# MainSchematic.net
KiCad netlist of a schematic drawn in Altium Designer
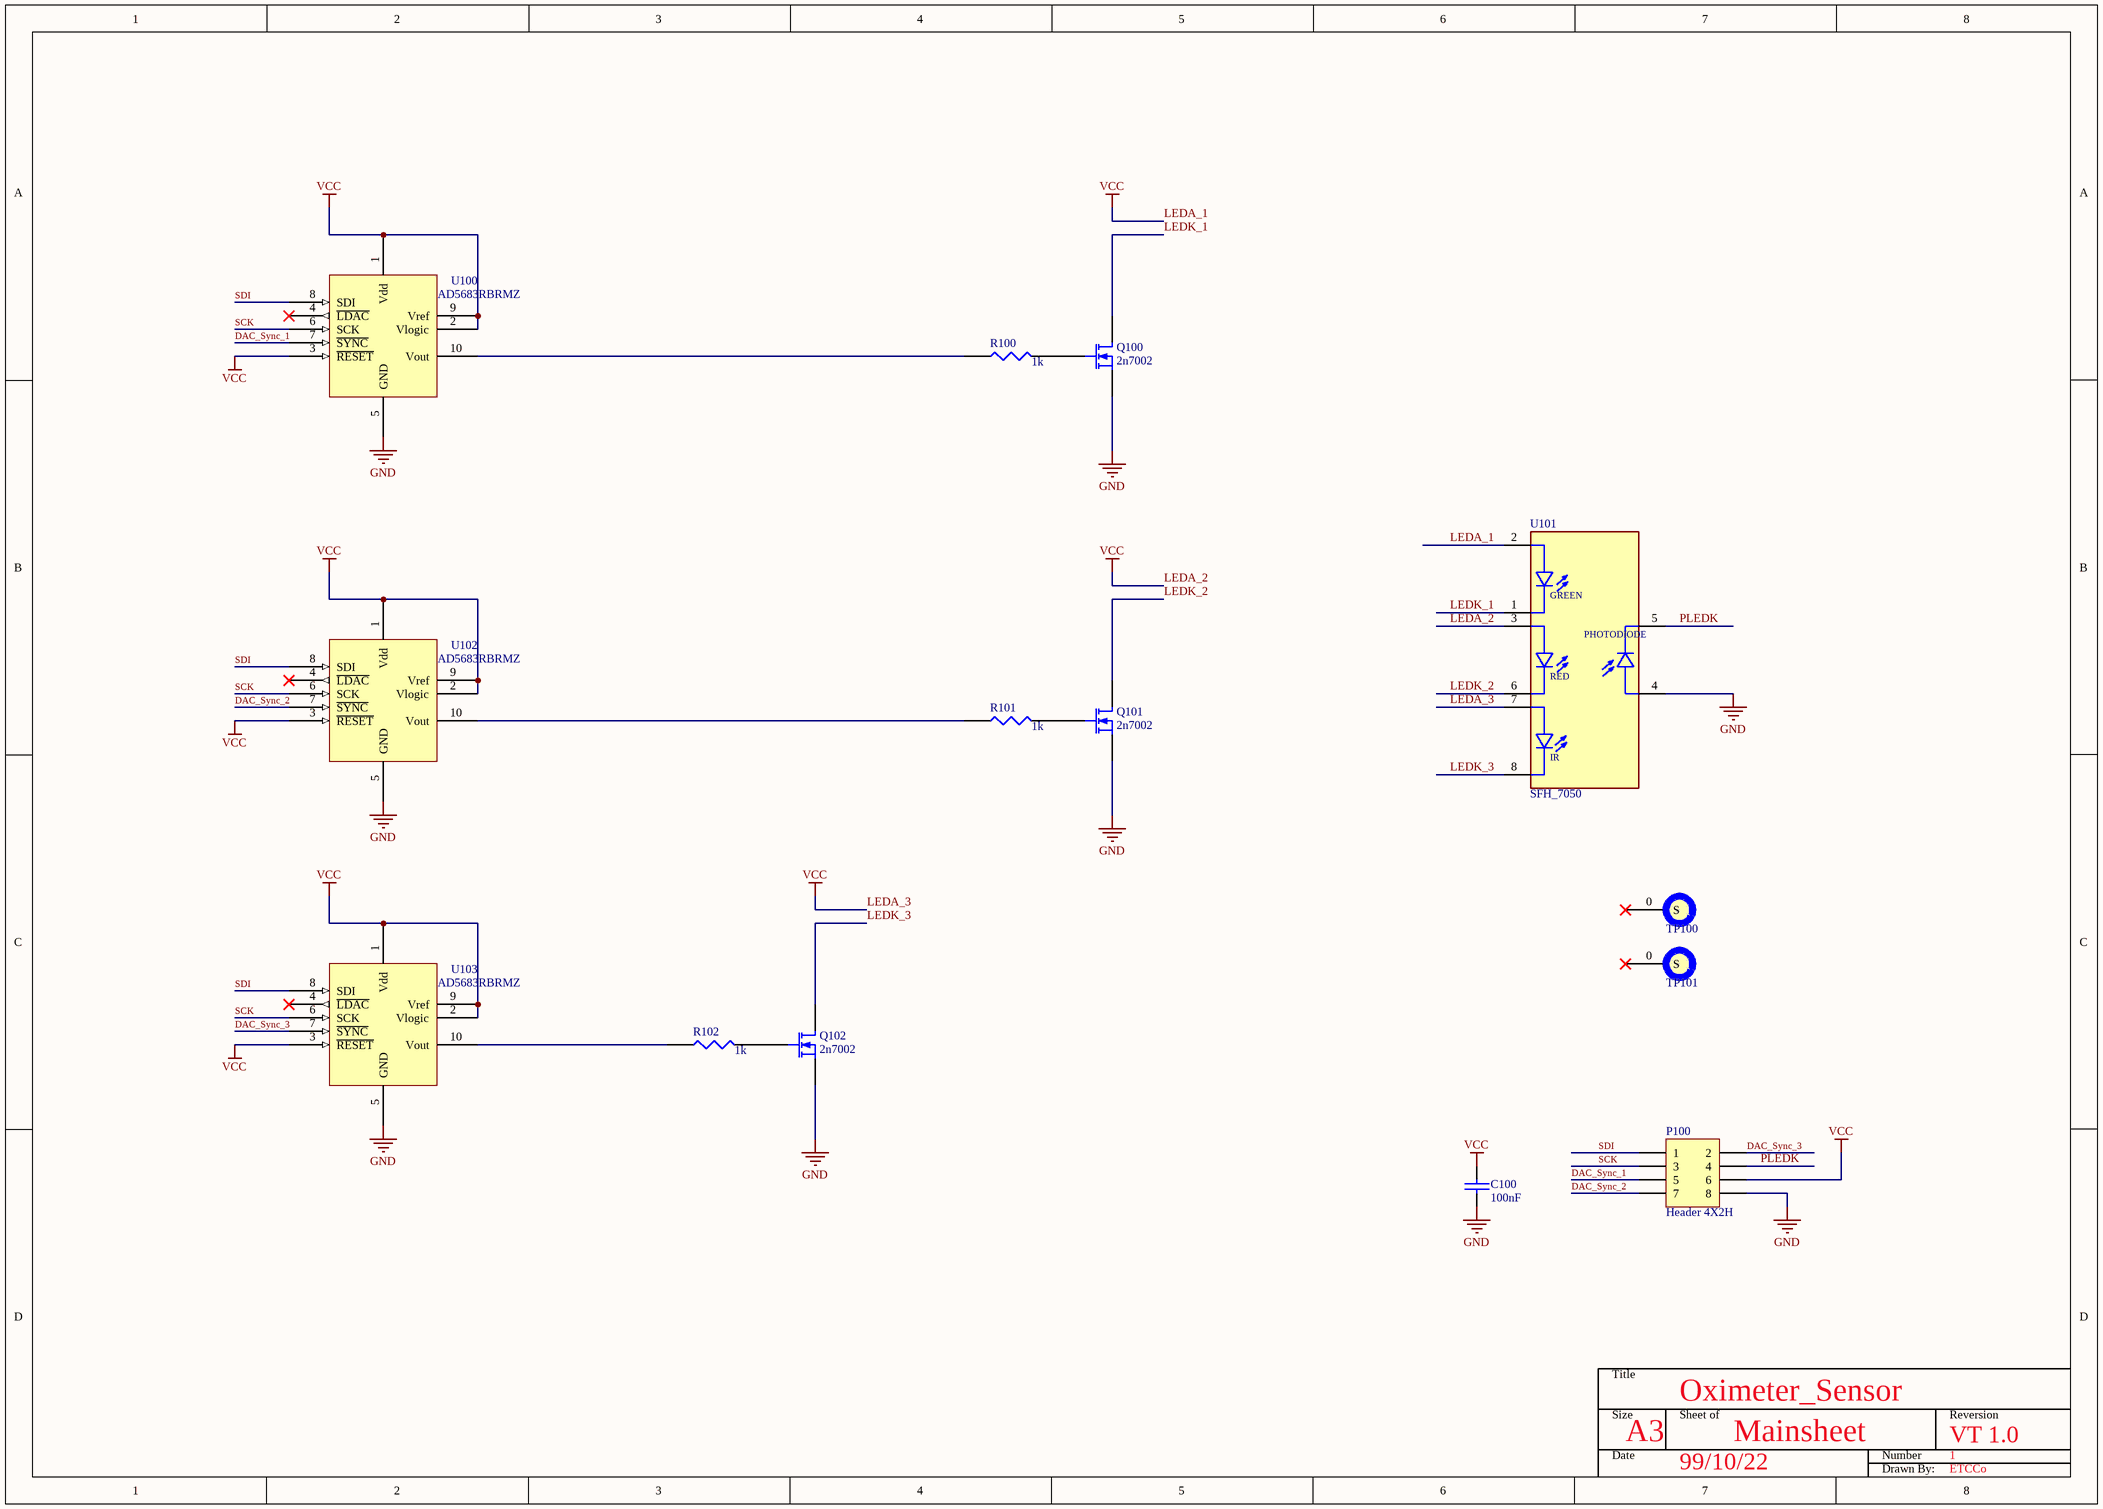
[diagram p0: MainSchematic.SchDoc]

(export (version "E")
  (design (tool "Eeschema 10.0.6"))
  (components
    (comp (ref "C100")
      (value "100nF")
      (footprint "0603-2")
      (description "Capacitor")
      (libsource (lib "*") (part "CAP"))
    )
    (comp (ref "P100")
      (value "Header 4X2H")
      (footprint "HDR2X4_edited")
      (description "Header, 4-Pin, Dual row, Right Angle")
      (fields (field (name "PUBLISHER") "Altium Limited"))
      (libsource (lib "Miscellaneous Connectors") (part "Header 4X2H"))
    )
    (comp (ref "Q100")
      (value "2n7002")
      (footprint "a_SOT23")
      (description "N-Channel MOSFET")
      (fields (field (name "PUBLISHER") "Altium Limited"))
      (libsource (lib "Miscellaneous Devices") (part "MOSFET-N"))
    )
    (comp (ref "Q101")
      (value "2n7002")
      (footprint "a_SOT23")
      (description "N-Channel MOSFET")
      (fields (field (name "PUBLISHER") "Altium Limited"))
      (libsource (lib "Miscellaneous Devices") (part "MOSFET-N"))
    )
    (comp (ref "Q102")
      (value "2n7002")
      (footprint "a_SOT23")
      (description "N-Channel MOSFET")
      (fields (field (name "PUBLISHER") "Altium Limited"))
      (libsource (lib "Miscellaneous Devices") (part "MOSFET-N"))
    )
    (comp (ref "R100") (value "1k") (footprint "0603-2") (libsource (lib "*") (part "RES1")))
    (comp (ref "R101") (value "1k") (footprint "0603-2") (libsource (lib "*") (part "RES1")))
    (comp (ref "R102") (value "1k") (footprint "0603-2") (libsource (lib "*") (part "RES1")))
    (comp (ref "TP100") (value "HOLE") (footprint "A_Ert") (libsource (lib "RXD") (part "TP")))
    (comp (ref "TP101") (value "HOLE") (footprint "A_Ert") (libsource (lib "RXD") (part "TP")))
    (comp (ref "U100")
      (value "AD5683RBRMZ")
      (footprint "MSOP-10")
      (description "Tiny 16-/14-/12-Bit SPI nanoDAC+, with  ±2 (16-Bit) LSB INL and 2 ppm/°C Reference")
      (libsource (lib "TGMP_SCH") (part "AD5683RBRMZ"))
    )
    (comp (ref "U101")
      (value "SFH_7050")
      (footprint "XDCR_SFH_7050")
      (description "Salida de voltaje del sensor de ox?­metro / frecuencia card?­aca")
      (fields (field (name "DIGI-KEY_PART_NUMBER") "475-3346-1-ND") (field (name "MP") "SFH 7050"))
      (libsource (lib "SnapEDAsch") (part "SFH_7050"))
    )
    (comp (ref "U102")
      (value "AD5683RBRMZ")
      (footprint "MSOP-10")
      (description "Tiny 16-/14-/12-Bit SPI nanoDAC+, with  ±2 (16-Bit) LSB INL and 2 ppm/°C Reference")
      (libsource (lib "TGMP_SCH") (part "AD5683RBRMZ"))
    )
    (comp (ref "U103")
      (value "AD5683RBRMZ")
      (footprint "MSOP-10")
      (description "Tiny 16-/14-/12-Bit SPI nanoDAC+, with  ±2 (16-Bit) LSB INL and 2 ppm/°C Reference")
      (libsource (lib "TGMP_SCH") (part "AD5683RBRMZ"))
    )
  )
  (nets
    (net (code "1") (name "/DAC_Sync_1") (class "Default")
      (node (ref "P100") (pin "5") (pinfunction "5_5") (pintype "passive"))
      (node (ref "U100") (pin "7") (pinfunction "~{SYNC}_7") (pintype "input"))
    )
    (net (code "2") (name "/DAC_Sync_2") (class "Default")
      (node (ref "P100") (pin "7") (pinfunction "7_7") (pintype "passive"))
      (node (ref "U102") (pin "7") (pinfunction "~{SYNC}_7") (pintype "input"))
    )
    (net (code "3") (name "/DAC_Sync_3") (class "Default")
      (node (ref "P100") (pin "2") (pinfunction "2_2") (pintype "passive"))
      (node (ref "U103") (pin "7") (pinfunction "~{SYNC}_7") (pintype "input"))
    )
    (net (code "4") (name "/LEDK_1") (class "Default")
      (node (ref "Q100") (pin "3") (pinfunction "D_3") (pintype "passive"))
      (node (ref "U101") (pin "1") (pinfunction "GC_1") (pintype "passive"))
    )
    (net (code "5") (name "/LEDK_2") (class "Default")
      (node (ref "Q101") (pin "3") (pinfunction "D_3") (pintype "passive"))
      (node (ref "U101") (pin "6") (pinfunction "RC_6") (pintype "passive"))
    )
    (net (code "6") (name "/LEDK_3") (class "Default")
      (node (ref "Q102") (pin "3") (pinfunction "D_3") (pintype "passive"))
      (node (ref "U101") (pin "8") (pinfunction "IC_8") (pintype "passive"))
    )
    (net (code "7") (name "/PLEDK") (class "Default")
      (node (ref "P100") (pin "4") (pinfunction "4_4") (pintype "passive"))
      (node (ref "U101") (pin "5") (pinfunction "PC_5") (pintype "passive"))
    )
    (net (code "8") (name "/SCK") (class "Default")
      (node (ref "P100") (pin "3") (pinfunction "3_3") (pintype "passive"))
      (node (ref "U100") (pin "6") (pinfunction "SCK_6") (pintype "input"))
      (node (ref "U102") (pin "6") (pinfunction "SCK_6") (pintype "input"))
      (node (ref "U103") (pin "6") (pinfunction "SCK_6") (pintype "input"))
    )
    (net (code "9") (name "/SDI") (class "Default")
      (node (ref "P100") (pin "1") (pinfunction "1_1") (pintype "passive"))
      (node (ref "U100") (pin "8") (pinfunction "SDI_8") (pintype "input"))
      (node (ref "U102") (pin "8") (pinfunction "SDI_8") (pintype "input"))
      (node (ref "U103") (pin "8") (pinfunction "SDI_8") (pintype "input"))
    )
    (net (code "10") (name "GND") (class "Default")
      (node (ref "C100") (pin "2") (pinfunction "2_2") (pintype "passive"))
      (node (ref "P100") (pin "8") (pinfunction "8_8") (pintype "passive"))
      (node (ref "Q100") (pin "2") (pinfunction "S_2") (pintype "passive"))
      (node (ref "Q101") (pin "2") (pinfunction "S_2") (pintype "passive"))
      (node (ref "Q102") (pin "2") (pinfunction "S_2") (pintype "passive"))
      (node (ref "U100") (pin "5") (pinfunction "GND_5") (pintype "power_in"))
      (node (ref "U101") (pin "4") (pinfunction "PA_4") (pintype "passive"))
      (node (ref "U102") (pin "5") (pinfunction "GND_5") (pintype "power_in"))
      (node (ref "U103") (pin "5") (pinfunction "GND_5") (pintype "power_in"))
    )
    (net (code "11") (name "Net-(Q100-G)") (class "Default")
      (node (ref "Q100") (pin "1") (pinfunction "G_1") (pintype "passive"))
      (node (ref "R100") (pin "2") (pinfunction "2_2") (pintype "passive"))
    )
    (net (code "12") (name "Net-(Q101-G)") (class "Default")
      (node (ref "Q101") (pin "1") (pinfunction "G_1") (pintype "passive"))
      (node (ref "R101") (pin "2") (pinfunction "2_2") (pintype "passive"))
    )
    (net (code "13") (name "Net-(Q102-G)") (class "Default")
      (node (ref "Q102") (pin "1") (pinfunction "G_1") (pintype "passive"))
      (node (ref "R102") (pin "2") (pinfunction "2_2") (pintype "passive"))
    )
    (net (code "14") (name "Net-(U100-Vout)") (class "Default")
      (node (ref "R100") (pin "1") (pinfunction "1_1") (pintype "passive"))
      (node (ref "U100") (pin "10") (pinfunction "Vout_10") (pintype "power_in"))
    )
    (net (code "15") (name "Net-(U102-Vout)") (class "Default")
      (node (ref "R101") (pin "1") (pinfunction "1_1") (pintype "passive"))
      (node (ref "U102") (pin "10") (pinfunction "Vout_10") (pintype "power_in"))
    )
    (net (code "16") (name "Net-(U103-Vout)") (class "Default")
      (node (ref "R102") (pin "1") (pinfunction "1_1") (pintype "passive"))
      (node (ref "U103") (pin "10") (pinfunction "Vout_10") (pintype "power_in"))
    )
    (net (code "17") (name "VCC") (class "Default")
      (node (ref "C100") (pin "1") (pinfunction "1_1") (pintype "passive"))
      (node (ref "P100") (pin "6") (pinfunction "6_6") (pintype "passive"))
      (node (ref "U100") (pin "1") (pinfunction "Vdd_1") (pintype "power_in"))
      (node (ref "U100") (pin "2") (pinfunction "Vlogic_2") (pintype "power_in"))
      (node (ref "U100") (pin "3") (pinfunction "~{RESET}_3") (pintype "input"))
      (node (ref "U100") (pin "9") (pinfunction "Vref_9") (pintype "power_in"))
      (node (ref "U101") (pin "2") (pinfunction "GA_2") (pintype "passive"))
      (node (ref "U101") (pin "3") (pinfunction "RA_3") (pintype "passive"))
      (node (ref "U101") (pin "7") (pinfunction "IA_7") (pintype "passive"))
      (node (ref "U102") (pin "1") (pinfunction "Vdd_1") (pintype "power_in"))
      (node (ref "U102") (pin "2") (pinfunction "Vlogic_2") (pintype "power_in"))
      (node (ref "U102") (pin "3") (pinfunction "~{RESET}_3") (pintype "input"))
      (node (ref "U102") (pin "9") (pinfunction "Vref_9") (pintype "power_in"))
      (node (ref "U103") (pin "1") (pinfunction "Vdd_1") (pintype "power_in"))
      (node (ref "U103") (pin "2") (pinfunction "Vlogic_2") (pintype "power_in"))
      (node (ref "U103") (pin "3") (pinfunction "~{RESET}_3") (pintype "input"))
      (node (ref "U103") (pin "9") (pinfunction "Vref_9") (pintype "power_in"))
    )
    (net (code "18") (name "unconnected-(TP100-S-Pad0)") (class "Default")
      (node (ref "TP100") (pin "0") (pinfunction "S_0") (pintype "passive+no_connect"))
    )
    (net (code "19") (name "unconnected-(TP101-S-Pad0)") (class "Default")
      (node (ref "TP101") (pin "0") (pinfunction "S_0") (pintype "passive+no_connect"))
    )
    (net (code "20") (name "unconnected-(U100-~{LDAC}-Pad4)") (class "Default")
      (node (ref "U100") (pin "4") (pinfunction "~{LDAC}_4") (pintype "output+no_connect"))
    )
    (net (code "21") (name "unconnected-(U102-~{LDAC}-Pad4)") (class "Default")
      (node (ref "U102") (pin "4") (pinfunction "~{LDAC}_4") (pintype "output+no_connect"))
    )
    (net (code "22") (name "unconnected-(U103-~{LDAC}-Pad4)") (class "Default")
      (node (ref "U103") (pin "4") (pinfunction "~{LDAC}_4") (pintype "output+no_connect"))
    )
  )
)
